# v1_2sch.net
KiCad netlist of a schematic drawn in EAGLE
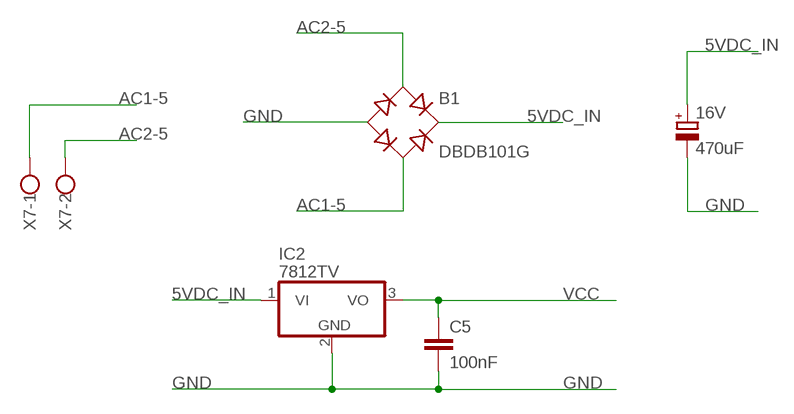
[diagram p0: schematic, sheet 1]
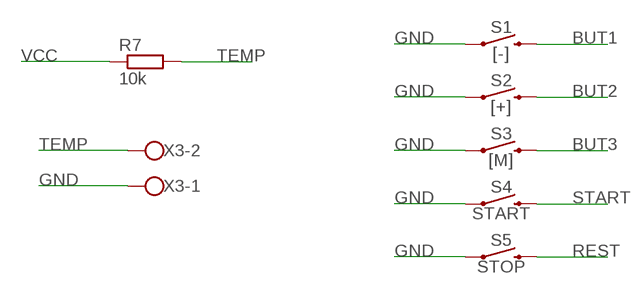
[diagram p1: schematic, sheet 2]
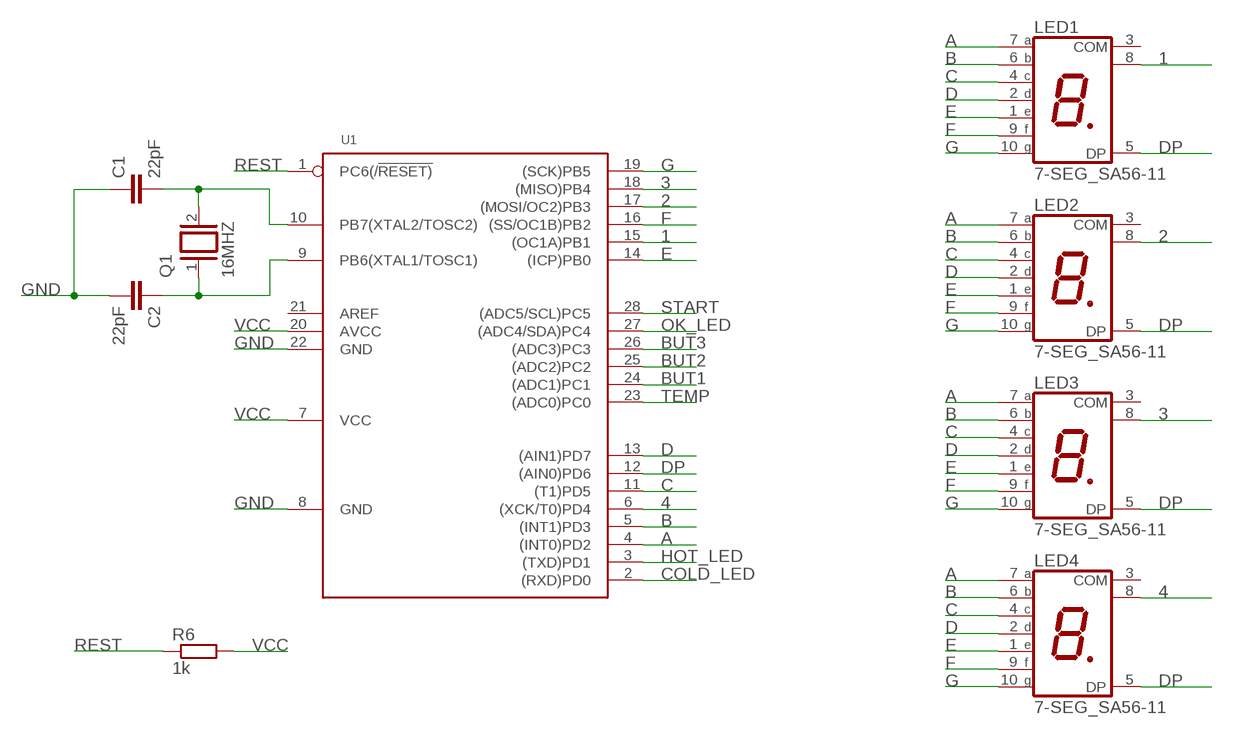
[diagram p2: schematic, sheet 3]
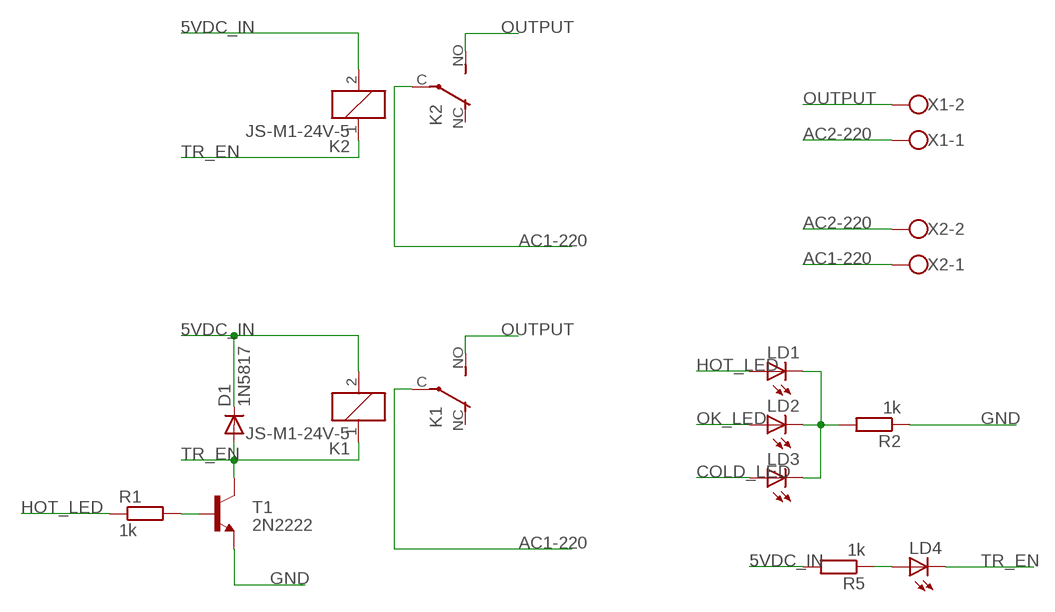
[diagram p3: schematic, sheet 4]

(export (version "E")
  (design (tool "Eeschema 10.0.6"))
  (components
    (comp (ref "C1")
      (value "22pF")
      (footprint "eagle-import:C050-025X075")
      (libsource (lib "eagle-import") (part "C-EU050-025X075"))
    )
    (comp (ref "C2")
      (value "22pF")
      (footprint "eagle-import:C050-025X075")
      (libsource (lib "eagle-import") (part "C-EU050-025X075"))
    )
    (comp (ref "LED1")
      (value "7-SEG_SA56-11")
      (footprint "eagle-import:SA56-11")
      (libsource (lib "eagle-import") (part "7-SEG_SA56-11"))
    )
    (comp (ref "LED2")
      (value "7-SEG_SA56-11")
      (footprint "eagle-import:SA56-11")
      (libsource (lib "eagle-import") (part "7-SEG_SA56-11"))
    )
    (comp (ref "LED3")
      (value "7-SEG_SA56-11")
      (footprint "eagle-import:SA56-11")
      (libsource (lib "eagle-import") (part "7-SEG_SA56-11"))
    )
    (comp (ref "LED4")
      (value "7-SEG_SA56-11")
      (footprint "eagle-import:SA56-11")
      (libsource (lib "eagle-import") (part "7-SEG_SA56-11"))
    )
    (comp (ref "Q1")
      (value "16MHZ")
      (footprint "eagle-import:QS")
      (libsource (lib "eagle-import") (part "XTAL/S"))
    )
    (comp (ref "R6")
      (value "1k")
      (footprint "eagle-import:0207_10")
      (libsource (lib "eagle-import") (part "R-EU_0207/10"))
    )
    (comp (ref "U1")
      (value "MCU-ATMEGA328P-PU(DIP28)")
      (footprint "eagle-import:DIP28-2.54-34.7X7.62MM")
      (fields (field (name "MPN") "ATMEGA328P-PU"))
      (libsource (lib "eagle-import") (part "MCU-ATMEGA328P-PU(DIP28)"))
    )
    (comp (ref "R7")
      (value "10k")
      (footprint "eagle-import:0207_10")
      (libsource (lib "eagle-import") (part "R-EU_0207/10"))
    )
    (comp (ref "S1")
      (value "[-]")
      (footprint "eagle-import:TACTILE_SWITCH_PTH_6.0MM")
      (libsource (lib "eagle-import") (part "MOMENTARY-SWITCH-SPST-PTH-6.0MM"))
    )
    (comp (ref "S2")
      (value "[+]")
      (footprint "eagle-import:TACTILE_SWITCH_PTH_6.0MM")
      (libsource (lib "eagle-import") (part "MOMENTARY-SWITCH-SPST-PTH-6.0MM"))
    )
    (comp (ref "S3")
      (value "[M]")
      (footprint "eagle-import:TACTILE_SWITCH_PTH_6.0MM")
      (libsource (lib "eagle-import") (part "MOMENTARY-SWITCH-SPST-PTH-6.0MM"))
    )
    (comp (ref "S4")
      (value "START")
      (footprint "eagle-import:TACTILE_SWITCH_PTH_6.0MM")
      (libsource (lib "eagle-import") (part "MOMENTARY-SWITCH-SPST-PTH-6.0MM"))
    )
    (comp (ref "S5")
      (value "STOP")
      (footprint "eagle-import:TACTILE_SWITCH_PTH_6.0MM")
      (libsource (lib "eagle-import") (part "MOMENTARY-SWITCH-SPST-PTH-6.0MM"))
    )
    (comp (ref "X3")
      (value "W237-102")
      (footprint "eagle-import:W237-102")
      (libsource (lib "eagle-import") (part "W237-102"))
    )
    (comp (ref "D1")
      (value "1N5817")
      (footprint "eagle-import:DO41-10")
      (libsource (lib "eagle-import") (part "1N4004"))
    )
    (comp (ref "K1")
      (value "JS-M1-24V-5")
      (footprint "eagle-import:JS-M")
      (fields (field (name "MF") "FARNELL") (field (name "MPN") "JSM1-12V-5"))
      (libsource (lib "eagle-import") (part "JS-M1-12V-5"))
    )
    (comp (ref "K2")
      (value "JS-M1-24V-5")
      (footprint "eagle-import:JS-M")
      (fields (field (name "MF") "FARNELL") (field (name "MPN") "JSM1-12V-5"))
      (libsource (lib "eagle-import") (part "JS-M1-12V-5"))
    )
    (comp (ref "LD1")
      (value "LED5MM")
      (footprint "eagle-import:LED5MM")
      (libsource (lib "eagle-import") (part "LED5MM"))
    )
    (comp (ref "LD2")
      (value "LED5MM")
      (footprint "eagle-import:LED5MM")
      (libsource (lib "eagle-import") (part "LED5MM"))
    )
    (comp (ref "LD3")
      (value "LED5MM")
      (footprint "eagle-import:LED5MM")
      (libsource (lib "eagle-import") (part "LED5MM"))
    )
    (comp (ref "LD4")
      (value "LED5MM")
      (footprint "eagle-import:LED5MM")
      (libsource (lib "eagle-import") (part "LED5MM"))
    )
    (comp (ref "R1")
      (value "1k")
      (footprint "eagle-import:0207_10")
      (libsource (lib "eagle-import") (part "R-EU_0207/10"))
    )
    (comp (ref "R2")
      (value "1k")
      (footprint "eagle-import:0207_10")
      (libsource (lib "eagle-import") (part "R-EU_0207/10"))
    )
    (comp (ref "R5")
      (value "1k")
      (footprint "eagle-import:0207_10")
      (libsource (lib "eagle-import") (part "R-EU_0207/10"))
    )
    (comp (ref "T1")
      (value "2N2222")
      (footprint "eagle-import:TO92-EBC-OVAL")
      (libsource (lib "eagle-import") (part "2N2222"))
    )
    (comp (ref "X1")
      (value "W237-102")
      (footprint "eagle-import:W237-102")
      (libsource (lib "eagle-import") (part "W237-102"))
    )
    (comp (ref "X2")
      (value "W237-102")
      (footprint "eagle-import:W237-102")
      (libsource (lib "eagle-import") (part "W237-102"))
    )
    (comp (ref "16V")
      (value "470uF")
      (footprint "eagle-import:E3,5-8")
      (libsource (lib "eagle-import") (part "CPOL-EUE3.5-8"))
    )
    (comp (ref "B1")
      (value "DBDB101G")
      (footprint "eagle-import:DB")
      (libsource (lib "eagle-import") (part "DB?GDB101"))
    )
    (comp (ref "C5")
      (value "100nF")
      (footprint "eagle-import:C050-025X075")
      (libsource (lib "eagle-import") (part "C-EU050-025X075"))
    )
    (comp (ref "IC2")
      (value "7812TV")
      (footprint "eagle-import:TO220V")
      (libsource (lib "eagle-import") (part "78TV12"))
    )
    (comp (ref "X7")
      (value "W237-102")
      (footprint "eagle-import:W237-102")
      (libsource (lib "eagle-import") (part "W237-102"))
    )
  )
  (nets
    (net (code "1") (name "1") (class "Default")
      (node (ref "LED1") (pin "8") (pinfunction "COM_8") (pintype "passive"))
      (node (ref "U1") (pin "15") (pinfunction "(OC1A)PB1_15") (pintype "bidirectional"))
    )
    (net (code "2") (name "2") (class "Default")
      (node (ref "LED2") (pin "8") (pinfunction "COM_8") (pintype "passive"))
      (node (ref "U1") (pin "17") (pinfunction "(MOSI/OC2)PB3_17") (pintype "bidirectional"))
    )
    (net (code "3") (name "3") (class "Default")
      (node (ref "LED3") (pin "8") (pinfunction "COM_8") (pintype "passive"))
      (node (ref "U1") (pin "18") (pinfunction "(MISO)PB4_18") (pintype "bidirectional"))
    )
    (net (code "4") (name "4") (class "Default")
      (node (ref "LED4") (pin "8") (pinfunction "COM_8") (pintype "passive"))
      (node (ref "U1") (pin "6") (pinfunction "(XCK/T0)PD4_6") (pintype "bidirectional"))
    )
    (net (code "5") (name "5VDC_IN") (class "Default")
      (node (ref "16V") (pin "+") (pinfunction "+_+") (pintype "passive"))
      (node (ref "B1") (pin "+") (pinfunction "+_+") (pintype "passive"))
      (node (ref "D1") (pin "C") (pinfunction "C_C") (pintype "passive"))
      (node (ref "IC2") (pin "1") (pinfunction "VI_1") (pintype "input"))
      (node (ref "K1") (pin "2") (pinfunction "2_2") (pintype "passive"))
      (node (ref "K2") (pin "2") (pinfunction "2_2") (pintype "passive"))
      (node (ref "R5") (pin "2") (pinfunction "2_2") (pintype "passive"))
    )
    (net (code "6") (name "A") (class "Default")
      (node (ref "LED1") (pin "7") (pinfunction "A_7") (pintype "passive"))
      (node (ref "LED2") (pin "7") (pinfunction "A_7") (pintype "passive"))
      (node (ref "LED3") (pin "7") (pinfunction "A_7") (pintype "passive"))
      (node (ref "LED4") (pin "7") (pinfunction "A_7") (pintype "passive"))
      (node (ref "U1") (pin "4") (pinfunction "(INT0)PD2_4") (pintype "bidirectional"))
    )
    (net (code "7") (name "AC1-5") (class "Default")
      (node (ref "B1") (pin "AC2") (pinfunction "AC2_AC2") (pintype "passive"))
      (node (ref "X7") (pin "1") (pinfunction "KL_1") (pintype "passive"))
    )
    (net (code "8") (name "AC1-220") (class "Default")
      (node (ref "K1") (pin "C") (pinfunction "P_C") (pintype "passive"))
      (node (ref "K2") (pin "C") (pinfunction "P_C") (pintype "passive"))
      (node (ref "X2") (pin "1") (pinfunction "KL_1") (pintype "passive"))
    )
    (net (code "9") (name "AC2-5") (class "Default")
      (node (ref "B1") (pin "AC1") (pinfunction "AC1_AC1") (pintype "passive"))
      (node (ref "X7") (pin "2") (pinfunction "KL_2") (pintype "passive"))
    )
    (net (code "10") (name "AC2-220") (class "Default")
      (node (ref "X1") (pin "1") (pinfunction "KL_1") (pintype "passive"))
      (node (ref "X2") (pin "2") (pinfunction "KL_2") (pintype "passive"))
    )
    (net (code "11") (name "B") (class "Default")
      (node (ref "LED1") (pin "6") (pinfunction "B_6") (pintype "passive"))
      (node (ref "LED2") (pin "6") (pinfunction "B_6") (pintype "passive"))
      (node (ref "LED3") (pin "6") (pinfunction "B_6") (pintype "passive"))
      (node (ref "LED4") (pin "6") (pinfunction "B_6") (pintype "passive"))
      (node (ref "U1") (pin "5") (pinfunction "(INT1)PD3_5") (pintype "bidirectional"))
    )
    (net (code "12") (name "BUT1") (class "Default")
      (node (ref "S1") (pin "3") (pinfunction "2_3") (pintype "passive"))
      (node (ref "U1") (pin "24") (pinfunction "(ADC1)PC1_24") (pintype "bidirectional"))
    )
    (net (code "13") (name "BUT2") (class "Default")
      (node (ref "S2") (pin "3") (pinfunction "2_3") (pintype "passive"))
      (node (ref "U1") (pin "25") (pinfunction "(ADC2)PC2_25") (pintype "bidirectional"))
    )
    (net (code "14") (name "BUT3") (class "Default")
      (node (ref "S3") (pin "3") (pinfunction "2_3") (pintype "passive"))
      (node (ref "U1") (pin "26") (pinfunction "(ADC3)PC3_26") (pintype "bidirectional"))
    )
    (net (code "15") (name "C") (class "Default")
      (node (ref "LED1") (pin "4") (pinfunction "C_4") (pintype "passive"))
      (node (ref "LED2") (pin "4") (pinfunction "C_4") (pintype "passive"))
      (node (ref "LED3") (pin "4") (pinfunction "C_4") (pintype "passive"))
      (node (ref "LED4") (pin "4") (pinfunction "C_4") (pintype "passive"))
      (node (ref "U1") (pin "11") (pinfunction "(T1)PD5_11") (pintype "bidirectional"))
    )
    (net (code "16") (name "COLD_LED") (class "Default")
      (node (ref "LD3") (pin "A") (pinfunction "A_A") (pintype "passive"))
      (node (ref "U1") (pin "2") (pinfunction "(RXD)PD0_2") (pintype "bidirectional"))
    )
    (net (code "17") (name "D") (class "Default")
      (node (ref "LED1") (pin "2") (pinfunction "D_2") (pintype "passive"))
      (node (ref "LED2") (pin "2") (pinfunction "D_2") (pintype "passive"))
      (node (ref "LED3") (pin "2") (pinfunction "D_2") (pintype "passive"))
      (node (ref "LED4") (pin "2") (pinfunction "D_2") (pintype "passive"))
      (node (ref "U1") (pin "13") (pinfunction "(AIN1)PD7_13") (pintype "bidirectional"))
    )
    (net (code "18") (name "DP") (class "Default")
      (node (ref "LED1") (pin "5") (pinfunction "DP_5") (pintype "passive"))
      (node (ref "LED2") (pin "5") (pinfunction "DP_5") (pintype "passive"))
      (node (ref "LED3") (pin "5") (pinfunction "DP_5") (pintype "passive"))
      (node (ref "LED4") (pin "5") (pinfunction "DP_5") (pintype "passive"))
      (node (ref "U1") (pin "12") (pinfunction "(AIN0)PD6_12") (pintype "bidirectional"))
    )
    (net (code "19") (name "E") (class "Default")
      (node (ref "LED1") (pin "1") (pinfunction "E_1") (pintype "passive"))
      (node (ref "LED2") (pin "1") (pinfunction "E_1") (pintype "passive"))
      (node (ref "LED3") (pin "1") (pinfunction "E_1") (pintype "passive"))
      (node (ref "LED4") (pin "1") (pinfunction "E_1") (pintype "passive"))
      (node (ref "U1") (pin "14") (pinfunction "(ICP)PB0_14") (pintype "bidirectional"))
    )
    (net (code "20") (name "F") (class "Default")
      (node (ref "LED1") (pin "9") (pinfunction "F_9") (pintype "passive"))
      (node (ref "LED2") (pin "9") (pinfunction "F_9") (pintype "passive"))
      (node (ref "LED3") (pin "9") (pinfunction "F_9") (pintype "passive"))
      (node (ref "LED4") (pin "9") (pinfunction "F_9") (pintype "passive"))
      (node (ref "U1") (pin "16") (pinfunction "(SS/OC1B)PB2_16") (pintype "bidirectional"))
    )
    (net (code "21") (name "G") (class "Default")
      (node (ref "LED1") (pin "10") (pinfunction "G_10") (pintype "passive"))
      (node (ref "LED2") (pin "10") (pinfunction "G_10") (pintype "passive"))
      (node (ref "LED3") (pin "10") (pinfunction "G_10") (pintype "passive"))
      (node (ref "LED4") (pin "10") (pinfunction "G_10") (pintype "passive"))
      (node (ref "U1") (pin "19") (pinfunction "(SCK)PB5_19") (pintype "bidirectional"))
    )
    (net (code "22") (name "GND") (class "Default")
      (node (ref "16V") (pin "-") (pinfunction "-_-") (pintype "passive"))
      (node (ref "B1") (pin "-") (pinfunction "-_-") (pintype "passive"))
      (node (ref "C1") (pin "1") (pinfunction "1_1") (pintype "passive"))
      (node (ref "C2") (pin "2") (pinfunction "2_2") (pintype "passive"))
      (node (ref "C5") (pin "2") (pinfunction "2_2") (pintype "passive"))
      (node (ref "IC2") (pin "2") (pinfunction "GND_2") (pintype "passive"))
      (node (ref "R2") (pin "1") (pinfunction "1_1") (pintype "passive"))
      (node (ref "S1") (pin "1") (pinfunction "1_1") (pintype "passive"))
      (node (ref "S2") (pin "1") (pinfunction "1_1") (pintype "passive"))
      (node (ref "S3") (pin "1") (pinfunction "1_1") (pintype "passive"))
      (node (ref "S4") (pin "1") (pinfunction "1_1") (pintype "passive"))
      (node (ref "S5") (pin "1") (pinfunction "1_1") (pintype "passive"))
      (node (ref "T1") (pin "E") (pinfunction "E_E") (pintype "passive"))
      (node (ref "U1") (pin "22") (pinfunction "GND_22") (pintype "bidirectional"))
      (node (ref "U1") (pin "8") (pinfunction "GND_8") (pintype "bidirectional"))
      (node (ref "X3") (pin "1") (pinfunction "KL_1") (pintype "passive"))
    )
    (net (code "23") (name "HOT_LED") (class "Default")
      (node (ref "LD1") (pin "A") (pinfunction "A_A") (pintype "passive"))
      (node (ref "R1") (pin "1") (pinfunction "1_1") (pintype "passive"))
      (node (ref "U1") (pin "3") (pinfunction "(TXD)PD1_3") (pintype "bidirectional"))
    )
    (net (code "24") (name "Net-(LD1-C)") (class "Default")
      (node (ref "LD1") (pin "K") (pinfunction "C_K") (pintype "passive"))
      (node (ref "LD2") (pin "K") (pinfunction "C_K") (pintype "passive"))
      (node (ref "LD3") (pin "K") (pinfunction "C_K") (pintype "passive"))
      (node (ref "R2") (pin "2") (pinfunction "2_2") (pintype "passive"))
    )
    (net (code "25") (name "Net-(LD4-PadA)") (class "Default")
      (node (ref "LD4") (pin "A") (pinfunction "A_A") (pintype "passive"))
      (node (ref "R5") (pin "1") (pinfunction "1_1") (pintype "passive"))
    )
    (net (code "26") (name "Net-(R1-Pad2)") (class "Default")
      (node (ref "R1") (pin "2") (pinfunction "2_2") (pintype "passive"))
      (node (ref "T1") (pin "B") (pinfunction "B_B") (pintype "passive"))
    )
    (net (code "27") (name "Net-(U1-PB6(XTAL1{slash}TOSC1))") (class "Default")
      (node (ref "C2") (pin "1") (pinfunction "1_1") (pintype "passive"))
      (node (ref "Q1") (pin "1") (pinfunction "1_1") (pintype "passive"))
      (node (ref "U1") (pin "9") (pinfunction "PB6(XTAL1/TOSC1)_9") (pintype "bidirectional"))
    )
    (net (code "28") (name "Net-(U1-PB7(XTAL2{slash}TOSC2))") (class "Default")
      (node (ref "C1") (pin "2") (pinfunction "2_2") (pintype "passive"))
      (node (ref "Q1") (pin "2") (pinfunction "2_2") (pintype "passive"))
      (node (ref "U1") (pin "10") (pinfunction "PB7(XTAL2/TOSC2)_10") (pintype "bidirectional"))
    )
    (net (code "29") (name "OK_LED") (class "Default")
      (node (ref "LD2") (pin "A") (pinfunction "A_A") (pintype "passive"))
      (node (ref "U1") (pin "27") (pinfunction "(ADC4/SDA)PC4_27") (pintype "bidirectional"))
    )
    (net (code "30") (name "OUTPUT") (class "Default")
      (node (ref "K1") (pin "NO") (pinfunction "S_NO") (pintype "passive"))
      (node (ref "K2") (pin "NO") (pinfunction "S_NO") (pintype "passive"))
      (node (ref "X1") (pin "2") (pinfunction "KL_2") (pintype "passive"))
    )
    (net (code "31") (name "REST") (class "Default")
      (node (ref "R6") (pin "1") (pinfunction "1_1") (pintype "passive"))
      (node (ref "S5") (pin "3") (pinfunction "2_3") (pintype "passive"))
      (node (ref "U1") (pin "1") (pinfunction "PC6(/~{RESET})_1") (pintype "bidirectional"))
    )
    (net (code "32") (name "START") (class "Default")
      (node (ref "S4") (pin "3") (pinfunction "2_3") (pintype "passive"))
      (node (ref "U1") (pin "28") (pinfunction "(ADC5/SCL)PC5_28") (pintype "bidirectional"))
    )
    (net (code "33") (name "TEMP") (class "Default")
      (node (ref "R7") (pin "2") (pinfunction "2_2") (pintype "passive"))
      (node (ref "U1") (pin "23") (pinfunction "(ADC0)PC0_23") (pintype "bidirectional"))
      (node (ref "X3") (pin "2") (pinfunction "KL_2") (pintype "passive"))
    )
    (net (code "34") (name "TR_EN") (class "Default")
      (node (ref "D1") (pin "A") (pinfunction "A_A") (pintype "passive"))
      (node (ref "K1") (pin "1") (pinfunction "1_1") (pintype "passive"))
      (node (ref "K2") (pin "1") (pinfunction "1_1") (pintype "passive"))
      (node (ref "LD4") (pin "K") (pinfunction "C_K") (pintype "passive"))
      (node (ref "T1") (pin "C") (pinfunction "C_C") (pintype "passive"))
    )
    (net (code "35") (name "VCC") (class "Default")
      (node (ref "C5") (pin "1") (pinfunction "1_1") (pintype "passive"))
      (node (ref "IC2") (pin "3") (pinfunction "VO_3") (pintype "passive"))
      (node (ref "R6") (pin "2") (pinfunction "2_2") (pintype "passive"))
      (node (ref "R7") (pin "1") (pinfunction "1_1") (pintype "passive"))
      (node (ref "U1") (pin "20") (pinfunction "AVCC_20") (pintype "bidirectional"))
      (node (ref "U1") (pin "7") (pinfunction "VCC_7") (pintype "bidirectional"))
    )
    (net (code "36") (name "unconnected-(K1B-O-PadNC)") (class "Default")
      (node (ref "K1") (pin "NC") (pinfunction "O_NC") (pintype "passive"))
    )
    (net (code "37") (name "unconnected-(K2B-O-PadNC)") (class "Default")
      (node (ref "K2") (pin "NC") (pinfunction "O_NC") (pintype "passive"))
    )
    (net (code "38") (name "unconnected-(LED1-COM-Pad3)") (class "Default")
      (node (ref "LED1") (pin "3") (pinfunction "COM_3") (pintype "passive"))
    )
    (net (code "39") (name "unconnected-(LED2-COM-Pad3)") (class "Default")
      (node (ref "LED2") (pin "3") (pinfunction "COM_3") (pintype "passive"))
    )
    (net (code "40") (name "unconnected-(LED3-COM-Pad3)") (class "Default")
      (node (ref "LED3") (pin "3") (pinfunction "COM_3") (pintype "passive"))
    )
    (net (code "41") (name "unconnected-(LED4-COM-Pad3)") (class "Default")
      (node (ref "LED4") (pin "3") (pinfunction "COM_3") (pintype "passive"))
    )
    (net (code "42") (name "unconnected-(U1-AREF-Pad21)") (class "Default")
      (node (ref "U1") (pin "21") (pinfunction "AREF_21") (pintype "bidirectional"))
    )
  )
)
